# Relay_Alert.net
KiCad netlist of a schematic drawn in Altium Designer
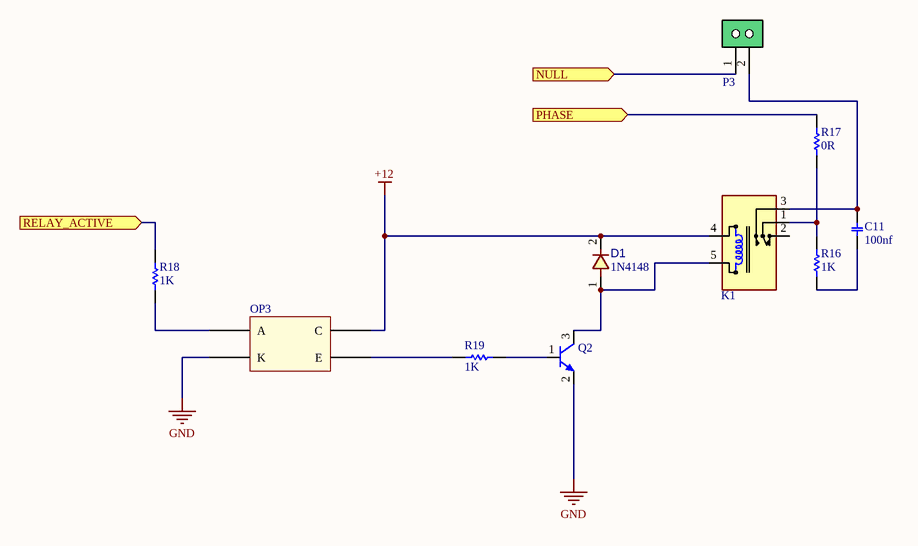
[diagram p0: Relay_Alert.SchDoc]

(export (version "E")
  (design (tool "Eeschema 10.0.6"))
  (components
    (comp (ref "C11")
      (value "100nf")
      (footprint "C_PLY_13X5")
      (description "Capacitor Polyester THD")
      (libsource (lib "Capacitor") (part "Capacitor Polyester THD"))
    )
    (comp (ref "D1")
      (value "1N4148")
      (footprint "D_SOD80")
      (description "DIODE, FAST SWTICHING, 0.3A, 0.5W")
      (fields (field (name "Comment") "1N4148 SMD"))
      (libsource (lib "Diode") (part "1N4148 SMD"))
    )
    (comp (ref "K1")
      (value "RELAY SPST 5 Pin Bache Millon")
      (footprint "REL_SPDT_5_1512")
      (description "Relay")
      (libsource (lib "Relay") (part "RELAY SPST 5 Pin Bache Millon"))
    )
    (comp (ref "OP3")
      (value "PC817")
      (footprint "PC817 SMD")
      (description "PC817 optocpler")
      (libsource (lib "IC") (part "PC817"))
    )
    (comp (ref "P3")
      (value "Phoenix 2")
      (footprint "PRKR2A")
      (libsource (lib "Connector") (part "Phoenix 2"))
    )
    (comp (ref "Q2")
      (value "BC847 NPN")
      (footprint "SOT-23")
      (description "BJT, NPN, 45v, 0.1A, SOT23")
      (libsource (lib "Transistor") (part "BC847 NPN"))
    )
    (comp (ref "R16")
      (value "1K")
      (footprint "R05W_AX05")
      (description "Resistor THD")
      (libsource (lib "Resistor") (part "Resistor THD"))
    )
    (comp (ref "R17")
      (value "0R")
      (footprint "SMD-1206-RES")
      (description "Resistor SMD 1206")
      (libsource (lib "Resistor") (part "Resistor SMD 1206"))
    )
    (comp (ref "R18")
      (value "1K")
      (footprint "SMD-1206-RES")
      (description "Resistor SMD 1206")
      (libsource (lib "Resistor") (part "Resistor SMD 1206"))
    )
    (comp (ref "R19")
      (value "1K")
      (footprint "SMD-1206-RES")
      (description "Resistor SMD 1206")
      (libsource (lib "Resistor") (part "Resistor SMD 1206"))
    )
  )
  (nets
    (net (code "1") (name "+12") (class "Default")
      (node (ref "D1") (pin "2") (pinfunction "2_2") (pintype "passive"))
      (node (ref "K1") (pin "4") (pinfunction "T1_4") (pintype "passive"))
      (node (ref "OP3") (pin "4") (pinfunction "C_4") (pintype "passive"))
    )
    (net (code "2") (name "/NULL") (class "Default")
      (node (ref "P3") (pin "1") (pinfunction "1_1") (pintype "passive"))
    )
    (net (code "3") (name "/PHASE") (class "Default")
      (node (ref "R17") (pin "2") (pinfunction "2_2") (pintype "passive"))
    )
    (net (code "4") (name "/RELAY_ACTIVE") (class "Default")
      (node (ref "R18") (pin "2") (pinfunction "2_2") (pintype "passive"))
    )
    (net (code "5") (name "GND") (class "Default")
      (node (ref "OP3") (pin "2") (pinfunction "K_2") (pintype "passive"))
      (node (ref "Q2") (pin "2") (pinfunction "E_2") (pintype "passive"))
    )
    (net (code "6") (name "Net-(C11-Pad1)") (class "Default")
      (node (ref "C11") (pin "1") (pinfunction "1_1") (pintype "passive"))
      (node (ref "R16") (pin "1") (pinfunction "1_1") (pintype "passive"))
    )
    (net (code "7") (name "Net-(K1-COM)") (class "Default")
      (node (ref "K1") (pin "1") (pinfunction "COM_1") (pintype "passive"))
      (node (ref "R16") (pin "2") (pinfunction "2_2") (pintype "passive"))
      (node (ref "R17") (pin "1") (pinfunction "1_1") (pintype "passive"))
    )
    (net (code "8") (name "Net-(K1-NO)") (class "Default")
      (node (ref "C11") (pin "2") (pinfunction "2_2") (pintype "passive"))
      (node (ref "K1") (pin "3") (pinfunction "NO_3") (pintype "passive"))
      (node (ref "P3") (pin "2") (pinfunction "2_2") (pintype "passive"))
    )
    (net (code "9") (name "Net-(K1-T2)") (class "Default")
      (node (ref "D1") (pin "1") (pinfunction "1_1") (pintype "passive"))
      (node (ref "K1") (pin "5") (pinfunction "T2_5") (pintype "passive"))
      (node (ref "Q2") (pin "3") (pinfunction "C_3") (pintype "passive"))
    )
    (net (code "10") (name "Net-(OP3-A)") (class "Default")
      (node (ref "OP3") (pin "1") (pinfunction "A_1") (pintype "passive"))
      (node (ref "R18") (pin "1") (pinfunction "1_1") (pintype "passive"))
    )
    (net (code "11") (name "Net-(OP3-E)") (class "Default")
      (node (ref "OP3") (pin "3") (pinfunction "E_3") (pintype "passive"))
      (node (ref "R19") (pin "1") (pinfunction "1_1") (pintype "passive"))
    )
    (net (code "12") (name "Net-(Q2-B)") (class "Default")
      (node (ref "Q2") (pin "1") (pinfunction "B_1") (pintype "passive"))
      (node (ref "R19") (pin "2") (pinfunction "2_2") (pintype "passive"))
    )
    (net (code "13") (name "unconnected-(K1-NC-Pad2)") (class "Default")
      (node (ref "K1") (pin "2") (pinfunction "NC_2") (pintype "passive"))
    )
  )
)
